# Sheet_1_2025-10-18.net
KiCad netlist of a schematic drawn in Altium Designer
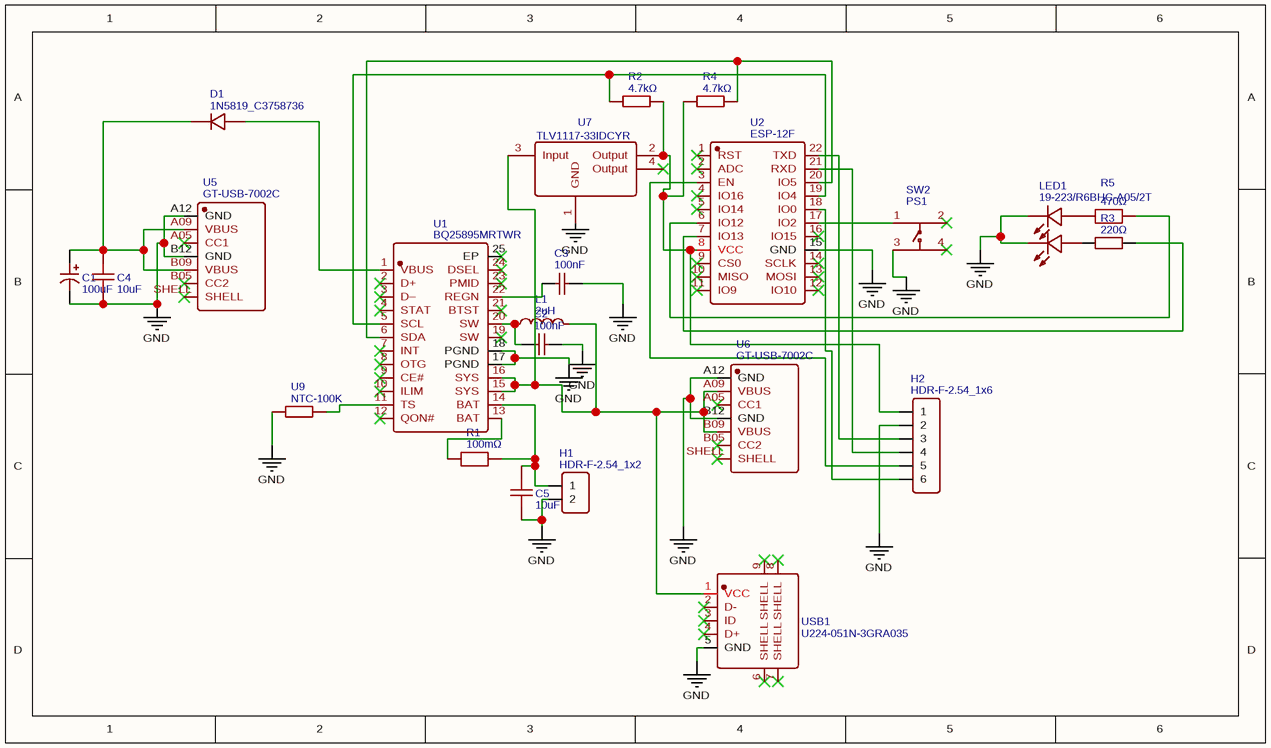
[diagram p0: Sheet_1_2025-10-18.schdoc]

(export (version "E")
  (design (tool "Eeschema 10.0.6"))
  (components
    (comp (ref "C1")
      (value "100uF")
      (fields
        (field (name "MANUFACTURER") "KNSCHA(科尼盛)")
        (field (name "MANUFACTURER PART") "RVT100UF35V67RV0034")
        (field (name "CONTRIBUTOR") "LCSC")
      )
      (libsource (lib "altium-import") (part "root_3_100uF_"))
    )
    (comp (ref "C2")
      (value "100nF")
      (fields (field (name "MANUFACTURER") "FH(风华)") (field (name "MANUFACTURER PART") "0402B104K250NT"))
      (libsource (lib "altium-import") (part "root_0_100nF_"))
    )
    (comp (ref "C3")
      (value "100nF")
      (fields (field (name "MANUFACTURER") "FH(风华)") (field (name "MANUFACTURER PART") "0402B104K250NT"))
      (libsource (lib "altium-import") (part "root_0_100nF_"))
    )
    (comp (ref "C4")
      (value "10uF")
      (fields
        (field (name "MANUFACTURER PART") "CL21A106KAYNNNE")
        (field (name "MANUFACTURER") "SAMSUNG(三星)")
      )
      (libsource (lib "altium-import") (part "root_3_10uF_"))
    )
    (comp (ref "C5")
      (value "10uF")
      (fields
        (field (name "MANUFACTURER PART") "CL21A106KAYNNNE")
        (field (name "MANUFACTURER") "SAMSUNG(三星)")
      )
      (libsource (lib "altium-import") (part "root_3_10uF_"))
    )
    (comp (ref "D1")
      (value "1N5819_C3758736")
      (fields
        (field (name "MANUFACTURER") "Taiwan Semiconductor(台湾半导体)")
        (field (name "MANUFACTURER PART") "1N5819")
        (field (name "CONTRIBUTOR") "lcsc")
      )
      (libsource (lib "altium-import") (part "root_0_1N5819_C3758736_"))
    )
    (comp (ref "H1")
      (value "HDR-F-2.54_1x2")
      (fields (field (name "CONTRIBUTOR") "LCEDA_Lib"))
      (libsource (lib "altium-import") (part "root_0_HDR-F-2.54_1x2_"))
    )
    (comp (ref "H2")
      (value "HDR-F-2.54_1x6")
      (fields (field (name "CONTRIBUTOR") "LCEDA_Lib"))
      (libsource (lib "altium-import") (part "root_0_HDR-F-2.54_1x6_"))
    )
    (comp (ref "L1")
      (value "2uH")
      (fields
        (field (name "MANUFACTURER") "KOHERelec(科或)")
        (field (name "MANUFACTURER PART") "FHC7030-2R0M")
        (field (name "CONTRIBUTOR") "LCSC")
      )
      (libsource (lib "altium-import") (part "root_0_2uH_"))
    )
    (comp (ref "LED1")
      (value "19-223/R6BHC-A05/2T")
      (fields (field (name "MANUFACTURER") "EVERLIGHT(亿光)") (field (name "CONTRIBUTOR") "LCSC"))
      (libsource (lib "altium-import") (part "root_0_19-223/R6BHC-A05/2T_"))
    )
    (comp (ref "R1")
      (value "100mΩ")
      (fields
        (field (name "MANUFACTURER") "Milliohm(毫欧)")
        (field (name "MANUFACTURER PART") "HoJLR2512-3W-100mR-1%")
        (field (name "CONTRIBUTOR") "lcsc")
      )
      (libsource (lib "altium-import") (part "root_0_100mΩ_"))
    )
    (comp (ref "R2")
      (value "4.7kΩ")
      (fields
        (field (name "MANUFACTURER") "KOA")
        (field (name "MANUFACTURER PART") "RN73H1JTTD4701B25")
        (field (name "CONTRIBUTOR") "LCSC")
      )
      (libsource (lib "altium-import") (part "root_0_4.7kΩ_"))
    )
    (comp (ref "R3")
      (value "220Ω")
      (fields
        (field (name "MANUFACTURER") "UNI-ROYAL(厚声)")
        (field (name "MANUFACTURER PART") "0603WAF2200T5E")
      )
      (libsource (lib "altium-import") (part "root_0_220Ω_"))
    )
    (comp (ref "R4")
      (value "4.7kΩ")
      (fields
        (field (name "MANUFACTURER") "KOA")
        (field (name "MANUFACTURER PART") "RN73H1JTTD4701B25")
        (field (name "CONTRIBUTOR") "LCSC")
      )
      (libsource (lib "altium-import") (part "root_0_4.7kΩ_"))
    )
    (comp (ref "R5")
      (value "470Ω")
      (fields
        (field (name "MANUFACTURER") "FOJAN(富捷)")
        (field (name "MANUFACTURER PART") "FRC0805J471 TS")
        (field (name "CONTRIBUTOR") "lcsc")
      )
      (libsource (lib "altium-import") (part "root_0_470Ω_"))
    )
    (comp (ref "SW2")
      (value "PS1")
      (fields
        (field (name "MANUFACTURER") "韩国韩荣")
        (field (name "MANUFACTURER PART") "K2-1157SP-I4SW-01")
        (field (name "CONTRIBUTOR") "mubashirimran41")
      )
      (libsource (lib "altium-import") (part "root_0_PS1_"))
    )
    (comp (ref "U1")
      (value "BQ25895MRTWR")
      (fields (field (name "MANUFACTURER") "TI(德州仪器)") (field (name "CONTRIBUTOR") "LCSC"))
      (libsource (lib "altium-import") (part "root_0_BQ25895MRTWR_"))
    )
    (comp (ref "U2")
      (value "ESP-12F")
      (fields (field (name "MANUFACTURER") "DOIT(四博智联)") (field (name "CONTRIBUTOR") "lcsc"))
      (libsource (lib "altium-import") (part "root_0_ESP-12F_"))
    )
    (comp (ref "U5")
      (value "GT-USB-7002C")
      (fields (field (name "MANUFACTURER") "G-Switch(品赞)") (field (name "CONTRIBUTOR") "lcsc"))
      (libsource (lib "altium-import") (part "root_0_GT-USB-7002C_"))
    )
    (comp (ref "U6")
      (value "GT-USB-7002C")
      (fields (field (name "MANUFACTURER") "G-Switch(品赞)") (field (name "CONTRIBUTOR") "lcsc"))
      (libsource (lib "altium-import") (part "root_0_GT-USB-7002C_"))
    )
    (comp (ref "U7")
      (value "TLV1117-33IDCYR")
      (fields (field (name "MANUFACTURER") "TI(德州仪器)"))
      (libsource (lib "altium-import") (part "root_0_TLV1117-33IDCYR_"))
    )
    (comp (ref "U9")
      (value "NTC-100K")
      (fields (field (name "CONTRIBUTOR") "lcsc"))
      (libsource (lib "altium-import") (part "root_0_NTC-100K_"))
    )
    (comp (ref "USB1")
      (value "U224-051N-3GRA035")
      (fields (field (name "MANUFACTURER") "XKB Connectivity(中国星坤)") (field (name "CONTRIBUTOR") "lcsc"))
      (libsource (lib "altium-import") (part "root_0_U224-051N-3GRA035_"))
    )
  )
  (nets
    (net (code "1") (name "GND") (class "Default")
      (node (ref "C1") (pin "2") (pinfunction "2_2") (pintype "passive"))
      (node (ref "C2") (pin "2") (pinfunction "2_2") (pintype "passive"))
      (node (ref "C3") (pin "2") (pinfunction "2_2") (pintype "passive"))
      (node (ref "C4") (pin "2") (pinfunction "2_2") (pintype "passive"))
      (node (ref "C5") (pin "2") (pinfunction "2_2") (pintype "passive"))
      (node (ref "H1") (pin "2") (pinfunction "2_2") (pintype "passive"))
      (node (ref "H2") (pin "2") (pinfunction "2_2") (pintype "passive"))
      (node (ref "LED1") (pin "2") (pinfunction "C_2") (pintype "passive"))
      (node (ref "LED1") (pin "4") (pinfunction "C_4") (pintype "passive"))
      (node (ref "SW2") (pin "3") (pinfunction "3_3") (pintype "passive"))
      (node (ref "U1") (pin "17") (pinfunction "PGND_17") (pintype "passive"))
      (node (ref "U1") (pin "18") (pinfunction "PGND_18") (pintype "passive"))
      (node (ref "U2") (pin "15") (pinfunction "GND_15") (pintype "passive"))
      (node (ref "U5") (pin "A12") (pinfunction "GND_A12") (pintype "passive"))
      (node (ref "U5") (pin "B12") (pinfunction "GND_B12") (pintype "passive"))
      (node (ref "U6") (pin "A12") (pinfunction "GND_A12") (pintype "passive"))
      (node (ref "U6") (pin "B12") (pinfunction "GND_B12") (pintype "passive"))
      (node (ref "U7") (pin "1") (pinfunction "GND_1") (pintype "passive"))
      (node (ref "U9") (pin "1") (pinfunction "1_1") (pintype "passive"))
      (node (ref "USB1") (pin "5") (pinfunction "GND_5") (pintype "passive"))
    )
    (net (code "2") (name "Net-(C2-Pad1)") (class "Default")
      (node (ref "C2") (pin "1") (pinfunction "1_1") (pintype "passive"))
      (node (ref "L1") (pin "1") (pinfunction "1_1") (pintype "passive"))
      (node (ref "U1") (pin "20") (pinfunction "SW_20") (pintype "passive"))
    )
    (net (code "3") (name "Net-(C5-Pad1)") (class "Default")
      (node (ref "C5") (pin "1") (pinfunction "1_1") (pintype "passive"))
      (node (ref "H1") (pin "1") (pinfunction "1_1") (pintype "passive"))
      (node (ref "R1") (pin "2") (pinfunction "2_2") (pintype "passive"))
      (node (ref "U1") (pin "14") (pinfunction "BAT_14") (pintype "passive"))
    )
    (net (code "4") (name "Net-(D1-A)") (class "Default")
      (node (ref "D1") (pin "1") (pinfunction "A_1") (pintype "passive"))
      (node (ref "U1") (pin "1") (pinfunction "VBUS_1") (pintype "passive"))
    )
    (net (code "5") (name "Net-(D1-K)") (class "Default")
      (node (ref "C1") (pin "1") (pinfunction "1_1") (pintype "passive"))
      (node (ref "C4") (pin "1") (pinfunction "1_1") (pintype "passive"))
      (node (ref "D1") (pin "2") (pinfunction "K_2") (pintype "passive"))
      (node (ref "U5") (pin "A09") (pinfunction "VBUS_A09") (pintype "passive"))
      (node (ref "U5") (pin "B09") (pinfunction "VBUS_B09") (pintype "passive"))
    )
    (net (code "6") (name "Net-(LED1-A-Pad1)") (class "Default")
      (node (ref "LED1") (pin "1") (pinfunction "A_1") (pintype "passive"))
      (node (ref "R3") (pin "1") (pinfunction "1_1") (pintype "passive"))
    )
    (net (code "7") (name "Net-(LED1-A-Pad3)") (class "Default")
      (node (ref "LED1") (pin "3") (pinfunction "A_3") (pintype "passive"))
      (node (ref "R5") (pin "1") (pinfunction "1_1") (pintype "passive"))
    )
    (net (code "8") (name "Net-(R1-Pad1)") (class "Default")
      (node (ref "R1") (pin "1") (pinfunction "1_1") (pintype "passive"))
      (node (ref "U1") (pin "13") (pinfunction "BAT_13") (pintype "passive"))
    )
    (net (code "9") (name "Net-(U1-REGN)") (class "Default")
      (node (ref "C3") (pin "1") (pinfunction "1_1") (pintype "passive"))
      (node (ref "U1") (pin "22") (pinfunction "REGN_22") (pintype "passive"))
    )
    (net (code "10") (name "Net-(U1-SCL)") (class "Default")
      (node (ref "R2") (pin "1") (pinfunction "1_1") (pintype "passive"))
      (node (ref "U1") (pin "5") (pinfunction "SCL_5") (pintype "passive"))
      (node (ref "U2") (pin "19") (pinfunction "IO4_19") (pintype "passive"))
    )
    (net (code "11") (name "Net-(U1-SDA)") (class "Default")
      (node (ref "R4") (pin "2") (pinfunction "2_2") (pintype "passive"))
      (node (ref "U1") (pin "6") (pinfunction "SDA_6") (pintype "passive"))
      (node (ref "U2") (pin "20") (pinfunction "IO5_20") (pintype "passive"))
    )
    (net (code "12") (name "Net-(U1-TS)") (class "Default")
      (node (ref "U1") (pin "11") (pinfunction "TS_11") (pintype "passive"))
      (node (ref "U9") (pin "2") (pinfunction "2_2") (pintype "passive"))
    )
    (net (code "13") (name "Net-(U2-EN)") (class "Default")
      (node (ref "H2") (pin "5") (pinfunction "5_5") (pintype "passive"))
      (node (ref "U2") (pin "3") (pinfunction "EN_3") (pintype "passive"))
    )
    (net (code "14") (name "Net-(U2-IO0)") (class "Default")
      (node (ref "H2") (pin "6") (pinfunction "6_6") (pintype "passive"))
      (node (ref "U2") (pin "18") (pinfunction "IO0_18") (pintype "passive"))
    )
    (net (code "15") (name "Net-(U2-IO2)") (class "Default")
      (node (ref "SW2") (pin "1") (pinfunction "1_1") (pintype "passive"))
      (node (ref "U2") (pin "17") (pinfunction "IO2_17") (pintype "passive"))
    )
    (net (code "16") (name "Net-(U2-IO12)") (class "Default")
      (node (ref "R5") (pin "2") (pinfunction "2_2") (pintype "passive"))
      (node (ref "U2") (pin "6") (pinfunction "IO12_6") (pintype "passive"))
    )
    (net (code "17") (name "Net-(U2-IO13)") (class "Default")
      (node (ref "R3") (pin "2") (pinfunction "2_2") (pintype "passive"))
      (node (ref "U2") (pin "7") (pinfunction "IO13_7") (pintype "passive"))
    )
    (net (code "18") (name "Net-(U2-RXD)") (class "Default")
      (node (ref "H2") (pin "4") (pinfunction "4_4") (pintype "passive"))
      (node (ref "U2") (pin "21") (pinfunction "RXD_21") (pintype "passive"))
    )
    (net (code "19") (name "Net-(U2-TXD)") (class "Default")
      (node (ref "H2") (pin "3") (pinfunction "3_3") (pintype "passive"))
      (node (ref "U2") (pin "22") (pinfunction "TXD_22") (pintype "passive"))
    )
    (net (code "20") (name "Net-(U2-VCC)") (class "Default")
      (node (ref "H2") (pin "1") (pinfunction "1_1") (pintype "passive"))
      (node (ref "R2") (pin "2") (pinfunction "2_2") (pintype "passive"))
      (node (ref "R4") (pin "1") (pinfunction "1_1") (pintype "passive"))
      (node (ref "U2") (pin "8") (pinfunction "VCC_8") (pintype "passive"))
      (node (ref "U7") (pin "2") (pinfunction "Output_2") (pintype "passive"))
    )
    (net (code "21") (name "Net-(U7-Input)") (class "Default")
      (node (ref "L1") (pin "2") (pinfunction "2_2") (pintype "passive"))
      (node (ref "U1") (pin "15") (pinfunction "SYS_15") (pintype "passive"))
      (node (ref "U1") (pin "16") (pinfunction "SYS_16") (pintype "passive"))
      (node (ref "U6") (pin "A09") (pinfunction "VBUS_A09") (pintype "passive"))
      (node (ref "U6") (pin "B09") (pinfunction "VBUS_B09") (pintype "passive"))
      (node (ref "U7") (pin "3") (pinfunction "Input_3") (pintype "passive"))
      (node (ref "USB1") (pin "1") (pinfunction "VCC_1") (pintype "passive"))
    )
    (net (code "22") (name "unconnected-(SW2-Pad2)") (class "Default")
      (node (ref "SW2") (pin "2") (pinfunction "2_2") (pintype "passive+no_connect"))
    )
    (net (code "23") (name "unconnected-(SW2-Pad4)") (class "Default")
      (node (ref "SW2") (pin "4") (pinfunction "4_4") (pintype "passive+no_connect"))
    )
    (net (code "24") (name "unconnected-(U1-BTST-Pad21)") (class "Default")
      (node (ref "U1") (pin "21") (pinfunction "BTST_21") (pintype "passive+no_connect"))
    )
    (net (code "25") (name "unconnected-(U1-CE#-Pad9)") (class "Default")
      (node (ref "U1") (pin "9") (pinfunction "CE#_9") (pintype "passive+no_connect"))
    )
    (net (code "26") (name "unconnected-(U1-D+-Pad2)") (class "Default")
      (node (ref "U1") (pin "2") (pinfunction "D+_2") (pintype "passive+no_connect"))
    )
    (net (code "27") (name "unconnected-(U1-DSEL-Pad24)") (class "Default")
      (node (ref "U1") (pin "24") (pinfunction "DSEL_24") (pintype "passive+no_connect"))
    )
    (net (code "28") (name "unconnected-(U1-D–-Pad3)") (class "Default")
      (node (ref "U1") (pin "3") (pinfunction "D–_3") (pintype "passive+no_connect"))
    )
    (net (code "29") (name "unconnected-(U1-EP-Pad25)") (class "Default")
      (node (ref "U1") (pin "25") (pinfunction "EP_25") (pintype "passive+no_connect"))
    )
    (net (code "30") (name "unconnected-(U1-ILIM-Pad10)") (class "Default")
      (node (ref "U1") (pin "10") (pinfunction "ILIM_10") (pintype "passive+no_connect"))
    )
    (net (code "31") (name "unconnected-(U1-INT-Pad7)") (class "Default")
      (node (ref "U1") (pin "7") (pinfunction "INT_7") (pintype "passive+no_connect"))
    )
    (net (code "32") (name "unconnected-(U1-OTG-Pad8)") (class "Default")
      (node (ref "U1") (pin "8") (pinfunction "OTG_8") (pintype "passive+no_connect"))
    )
    (net (code "33") (name "unconnected-(U1-PMID-Pad23)") (class "Default")
      (node (ref "U1") (pin "23") (pinfunction "PMID_23") (pintype "passive+no_connect"))
    )
    (net (code "34") (name "unconnected-(U1-QON#-Pad12)") (class "Default")
      (node (ref "U1") (pin "12") (pinfunction "QON#_12") (pintype "passive+no_connect"))
    )
    (net (code "35") (name "unconnected-(U1-STAT-Pad4)") (class "Default")
      (node (ref "U1") (pin "4") (pinfunction "STAT_4") (pintype "passive+no_connect"))
    )
    (net (code "36") (name "unconnected-(U1-SW-Pad19)") (class "Default")
      (node (ref "U1") (pin "19") (pinfunction "SW_19") (pintype "passive+no_connect"))
    )
    (net (code "37") (name "unconnected-(U2-ADC-Pad2)") (class "Default")
      (node (ref "U2") (pin "2") (pinfunction "ADC_2") (pintype "passive+no_connect"))
    )
    (net (code "38") (name "unconnected-(U2-CS0-Pad9)") (class "Default")
      (node (ref "U2") (pin "9") (pinfunction "CS0_9") (pintype "passive+no_connect"))
    )
    (net (code "39") (name "unconnected-(U2-IO9-Pad11)") (class "Default")
      (node (ref "U2") (pin "11") (pinfunction "IO9_11") (pintype "passive+no_connect"))
    )
    (net (code "40") (name "unconnected-(U2-IO10-Pad12)") (class "Default")
      (node (ref "U2") (pin "12") (pinfunction "IO10_12") (pintype "passive+no_connect"))
    )
    (net (code "41") (name "unconnected-(U2-IO14-Pad5)") (class "Default")
      (node (ref "U2") (pin "5") (pinfunction "IO14_5") (pintype "passive+no_connect"))
    )
    (net (code "42") (name "unconnected-(U2-IO15-Pad16)") (class "Default")
      (node (ref "U2") (pin "16") (pinfunction "IO15_16") (pintype "passive+no_connect"))
    )
    (net (code "43") (name "unconnected-(U2-IO16-Pad4)") (class "Default")
      (node (ref "U2") (pin "4") (pinfunction "IO16_4") (pintype "passive+no_connect"))
    )
    (net (code "44") (name "unconnected-(U2-MISO-Pad10)") (class "Default")
      (node (ref "U2") (pin "10") (pinfunction "MISO_10") (pintype "passive+no_connect"))
    )
    (net (code "45") (name "unconnected-(U2-MOSI-Pad13)") (class "Default")
      (node (ref "U2") (pin "13") (pinfunction "MOSI_13") (pintype "passive+no_connect"))
    )
    (net (code "46") (name "unconnected-(U2-RST-Pad1)") (class "Default")
      (node (ref "U2") (pin "1") (pinfunction "RST_1") (pintype "passive+no_connect"))
    )
    (net (code "47") (name "unconnected-(U2-SCLK-Pad14)") (class "Default")
      (node (ref "U2") (pin "14") (pinfunction "SCLK_14") (pintype "passive+no_connect"))
    )
    (net (code "48") (name "unconnected-(U5-CC1-PadA05)") (class "Default")
      (node (ref "U5") (pin "A05") (pinfunction "CC1_A05") (pintype "passive+no_connect"))
    )
    (net (code "49") (name "unconnected-(U5-CC2-PadB05)") (class "Default")
      (node (ref "U5") (pin "B05") (pinfunction "CC2_B05") (pintype "passive+no_connect"))
    )
    (net (code "50") (name "unconnected-(U5-PadSHELL)") (class "Default")
      (node (ref "U5") (pin "SHELL") (pinfunction "SHELL_SHELL") (pintype "passive+no_connect"))
    )
    (net (code "51") (name "unconnected-(U6-CC1-PadA05)") (class "Default")
      (node (ref "U6") (pin "A05") (pinfunction "CC1_A05") (pintype "passive+no_connect"))
    )
    (net (code "52") (name "unconnected-(U6-CC2-PadB05)") (class "Default")
      (node (ref "U6") (pin "B05") (pinfunction "CC2_B05") (pintype "passive+no_connect"))
    )
    (net (code "53") (name "unconnected-(U6-PadSHELL)") (class "Default")
      (node (ref "U6") (pin "SHELL") (pinfunction "SHELL_SHELL") (pintype "passive+no_connect"))
    )
    (net (code "54") (name "unconnected-(U7-Output-Pad4)") (class "Default")
      (node (ref "U7") (pin "4") (pinfunction "Output_4") (pintype "passive+no_connect"))
    )
    (net (code "55") (name "unconnected-(USB1-D+-Pad4)") (class "Default")
      (node (ref "USB1") (pin "4") (pinfunction "D+_4") (pintype "passive+no_connect"))
    )
    (net (code "56") (name "unconnected-(USB1-D--Pad2)") (class "Default")
      (node (ref "USB1") (pin "2") (pinfunction "D-_2") (pintype "passive+no_connect"))
    )
    (net (code "57") (name "unconnected-(USB1-ID-Pad3)") (class "Default")
      (node (ref "USB1") (pin "3") (pinfunction "ID_3") (pintype "passive+no_connect"))
    )
    (net (code "58") (name "unconnected-(USB1-SHELL-Pad6)") (class "Default")
      (node (ref "USB1") (pin "6") (pinfunction "SHELL_6") (pintype "passive+no_connect"))
    )
    (net (code "59") (name "unconnected-(USB1-SHELL-Pad7)") (class "Default")
      (node (ref "USB1") (pin "7") (pinfunction "SHELL_7") (pintype "passive+no_connect"))
    )
    (net (code "60") (name "unconnected-(USB1-SHELL-Pad8)") (class "Default")
      (node (ref "USB1") (pin "8") (pinfunction "SHELL_8") (pintype "passive+no_connect"))
    )
    (net (code "61") (name "unconnected-(USB1-SHELL-Pad9)") (class "Default")
      (node (ref "USB1") (pin "9") (pinfunction "SHELL_9") (pintype "passive+no_connect"))
    )
  )
)
